# working.net
KiCad netlist of a schematic drawn in EAGLE
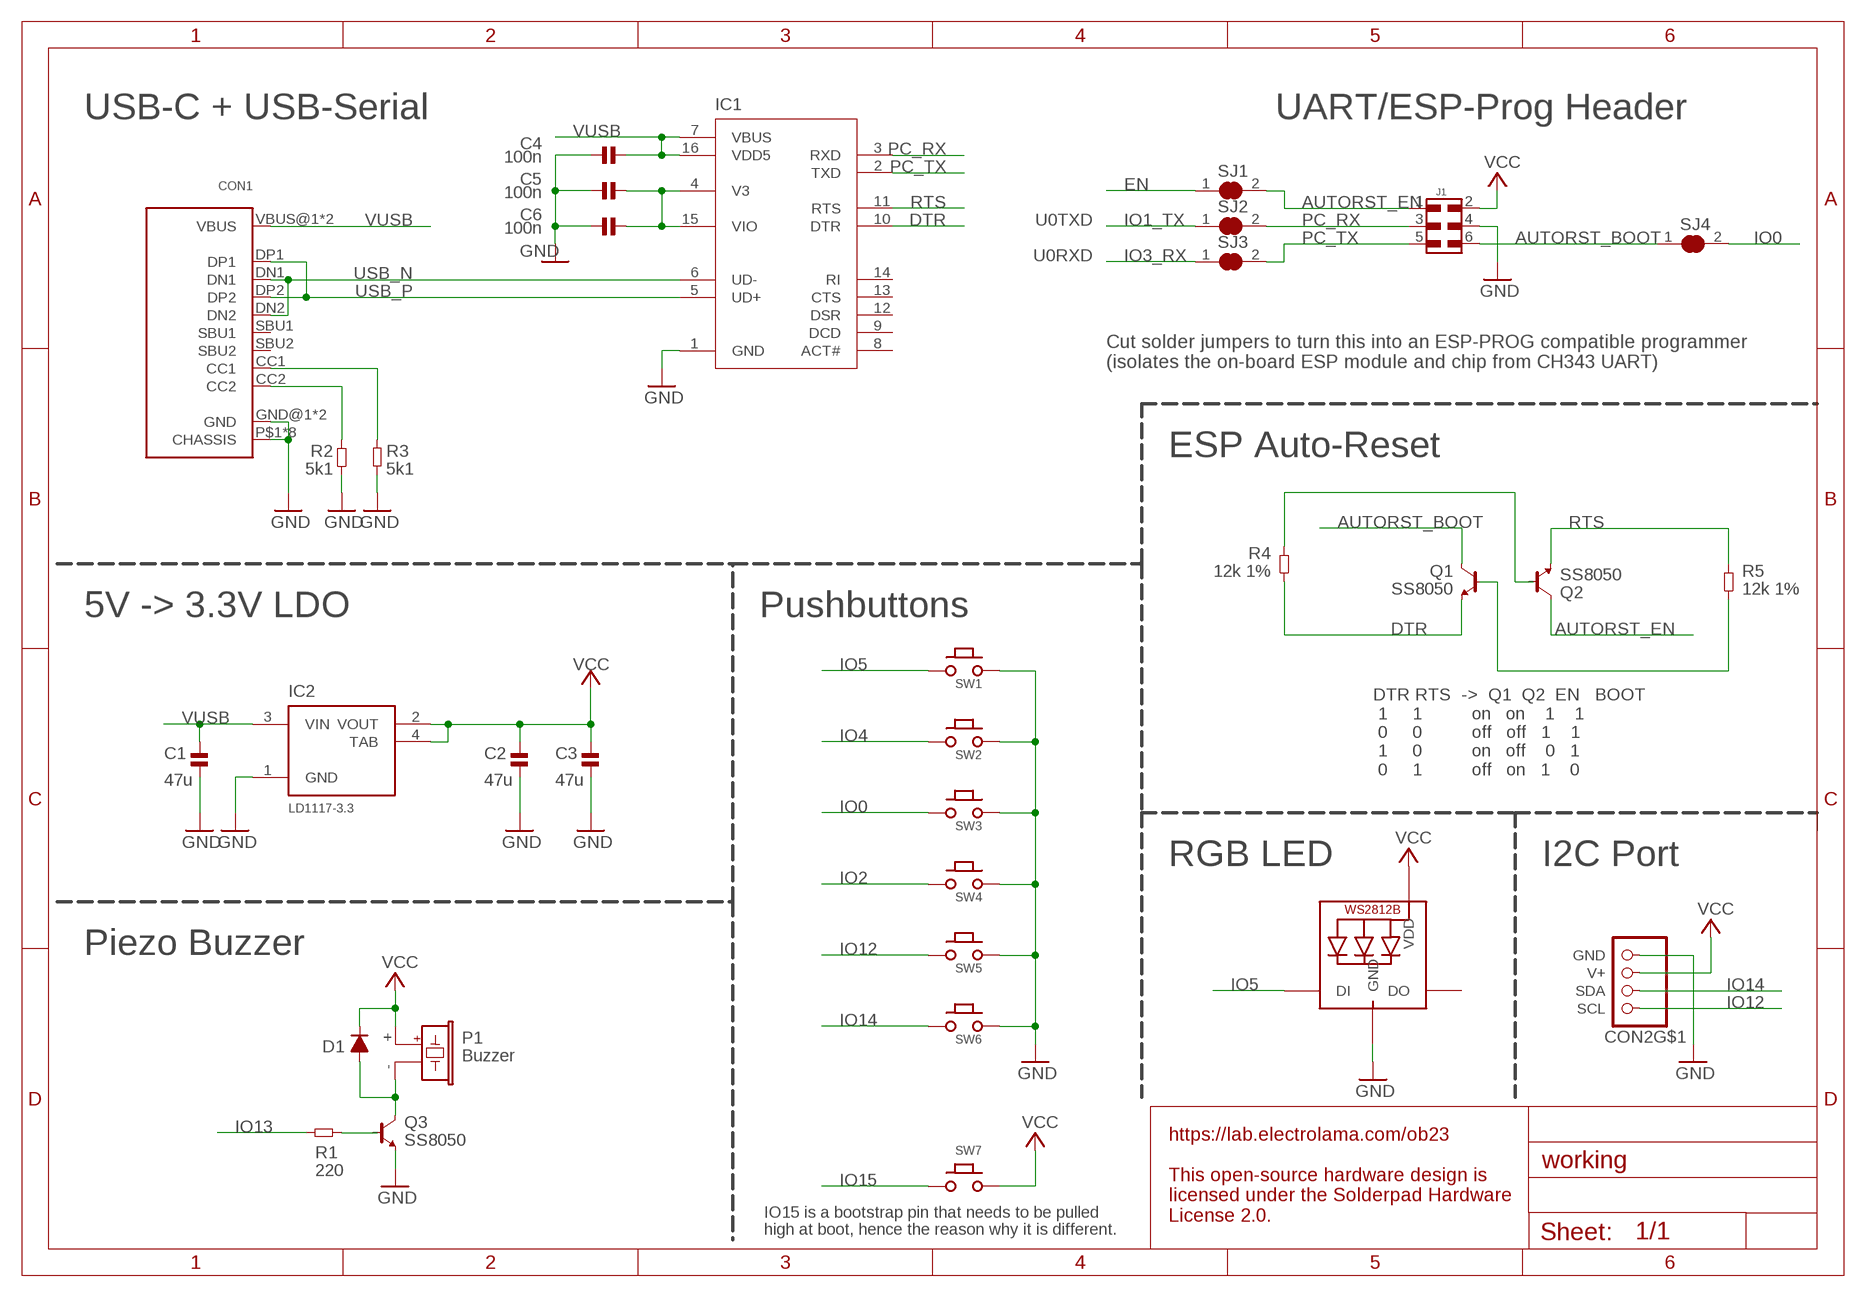
[diagram p0: schematic, sheet 1, part 1 of 2]
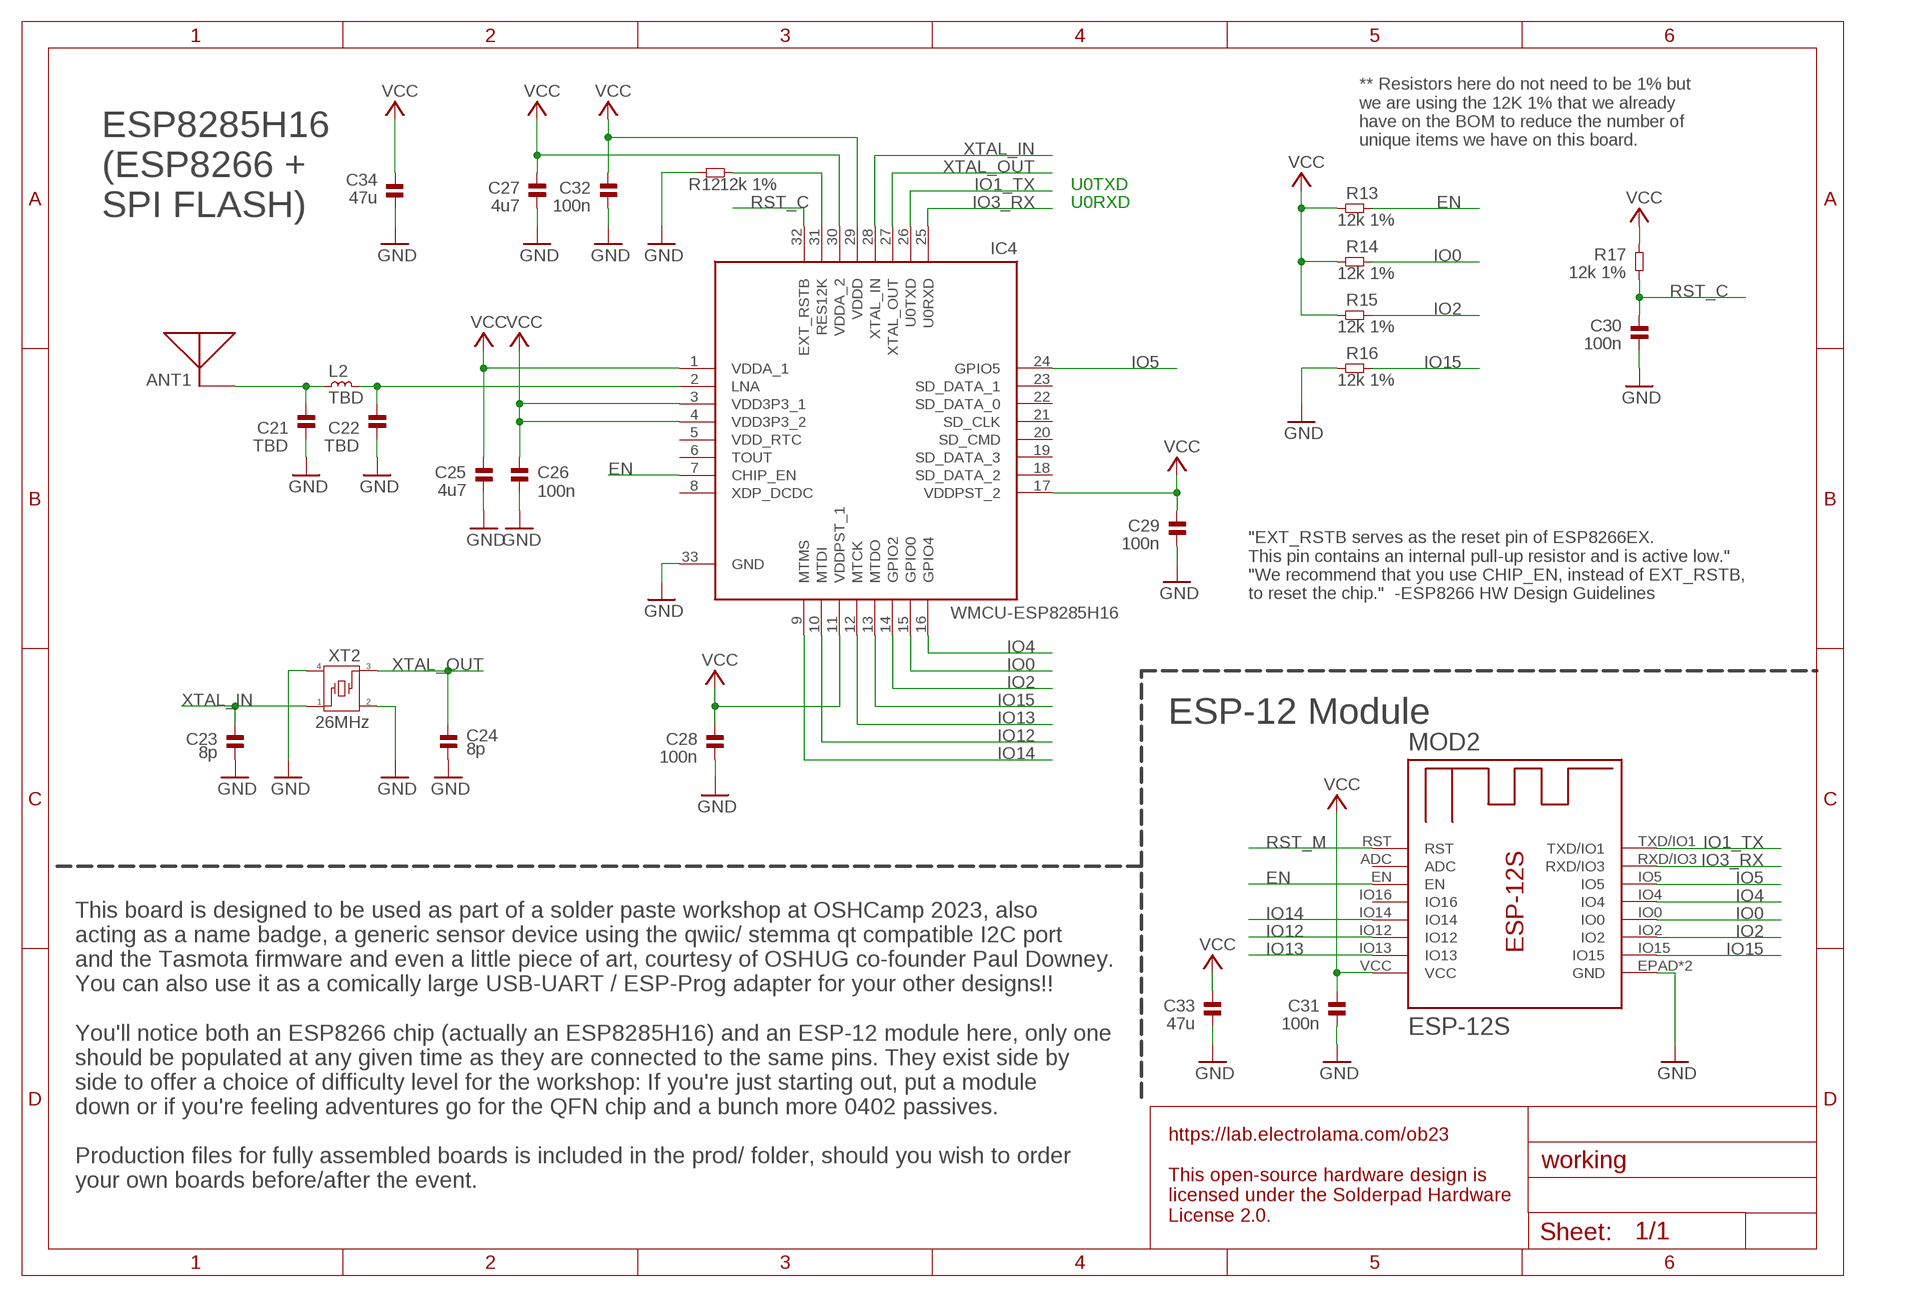
[diagram p1: schematic, sheet 1, part 2 of 2]

(export (version "E")
  (design (tool "Eeschema 10.0.6"))
  (components
    (comp (ref "ANT2")
      (value "ANT3216LL00R2400A")
      (footprint "eagle-import:YAGEO-ANT3216LL00R2400A")
      (libsource (lib "eagle-import") (part "ANT-CERAMIC-YAGEO-ANT3216LL00R2400A"))
    )
    (comp (ref "C1")
      (value "47u")
      (footprint "eagle-import:_PKG_C_1206")
      (fields (field (name "MPN") "CL31A476MPHNNNE"))
      (libsource (lib "eagle-import") (part "CAP-1206"))
    )
    (comp (ref "C2")
      (value "47u")
      (footprint "eagle-import:_PKG_C_1206")
      (fields (field (name "MPN") "CL31A476MPHNNNE"))
      (libsource (lib "eagle-import") (part "CAP-1206"))
    )
    (comp (ref "C3")
      (value "47u")
      (footprint "eagle-import:_PKG_C_1206")
      (fields (field (name "MPN") "CL31A476MPHNNNE"))
      (libsource (lib "eagle-import") (part "CAP-1206"))
    )
    (comp (ref "C4")
      (value "100n")
      (footprint "eagle-import:_PKG_C_0402")
      (libsource (lib "eagle-import") (part "CAP-0402"))
    )
    (comp (ref "C5")
      (value "100n")
      (footprint "eagle-import:_PKG_C_0402")
      (libsource (lib "eagle-import") (part "CAP-0402"))
    )
    (comp (ref "C6")
      (value "100n")
      (footprint "eagle-import:_PKG_C_0402")
      (libsource (lib "eagle-import") (part "CAP-0402"))
    )
    (comp (ref "C21")
      (value "TBD")
      (footprint "eagle-import:_PKG_C_0402_NOTHERMALS")
      (libsource (lib "eagle-import") (part "CAP-0402-NOTHERMALS"))
    )
    (comp (ref "C22")
      (value "TBD")
      (footprint "eagle-import:_PKG_C_0402_NOTHERMALS")
      (libsource (lib "eagle-import") (part "CAP-0402-NOTHERMALS"))
    )
    (comp (ref "C23")
      (value "8p")
      (footprint "eagle-import:_PKG_C_0402")
      (libsource (lib "eagle-import") (part "CAP-0402"))
    )
    (comp (ref "C24")
      (value "8p")
      (footprint "eagle-import:_PKG_C_0402")
      (libsource (lib "eagle-import") (part "CAP-0402"))
    )
    (comp (ref "C25")
      (value "4u7")
      (footprint "eagle-import:_PKG_C_0402_NOTHERMALS")
      (libsource (lib "eagle-import") (part "CAP-0402-NOTHERMALS"))
    )
    (comp (ref "C26")
      (value "100n")
      (footprint "eagle-import:_PKG_C_0402_NOTHERMALS")
      (libsource (lib "eagle-import") (part "CAP-0402-NOTHERMALS"))
    )
    (comp (ref "C27")
      (value "4u7")
      (footprint "eagle-import:_PKG_C_0402_NOTHERMALS")
      (libsource (lib "eagle-import") (part "CAP-0402-NOTHERMALS"))
    )
    (comp (ref "C28")
      (value "100n")
      (footprint "eagle-import:_PKG_C_0402_NOTHERMALS")
      (libsource (lib "eagle-import") (part "CAP-0402-NOTHERMALS"))
    )
    (comp (ref "C29")
      (value "100n")
      (footprint "eagle-import:_PKG_C_0402_NOTHERMALS")
      (libsource (lib "eagle-import") (part "CAP-0402-NOTHERMALS"))
    )
    (comp (ref "C30")
      (value "100n")
      (footprint "eagle-import:_PKG_C_0402_NOTHERMALS")
      (libsource (lib "eagle-import") (part "CAP-0402-NOTHERMALS"))
    )
    (comp (ref "C31")
      (value "100n")
      (footprint "eagle-import:_PKG_C_0402")
      (libsource (lib "eagle-import") (part "CAP-0402"))
    )
    (comp (ref "C32")
      (value "100n")
      (footprint "eagle-import:_PKG_C_0402_NOTHERMALS")
      (libsource (lib "eagle-import") (part "CAP-0402-NOTHERMALS"))
    )
    (comp (ref "C33")
      (value "47u")
      (footprint "eagle-import:_PKG_C_1206")
      (fields (field (name "MPN") "CL31A476MPHNNNE"))
      (libsource (lib "eagle-import") (part "CAP-1206"))
    )
    (comp (ref "C34")
      (value "47u")
      (footprint "eagle-import:_PKG_C_1206")
      (fields (field (name "MPN") "CL31A476MPHNNNE"))
      (libsource (lib "eagle-import") (part "CAP-1206"))
    )
    (comp (ref "CON1")
      (value "USBC_USB-C-12")
      (footprint "eagle-import:USBC_C-31-M-12")
      (libsource (lib "eagle-import") (part "USBC_USB-C-12"))
    )
    (comp (ref "CON2")
      (value "STEMMA_I2C_QT")
      (footprint "eagle-import:JST_SH4")
      (libsource (lib "eagle-import") (part "STEMMA_I2C_QT"))
    )
    (comp (ref "D1")
      (value "DIODE-SWITCHING-1N4148W")
      (footprint "eagle-import:_PKG_SOD123")
      (libsource (lib "eagle-import") (part "DIODE-SWITCHING-1N4148W"))
    )
    (comp (ref "IC1")
      (value "INTERFACE-CH343G")
      (footprint "eagle-import:_PKG_SOP16")
      (libsource (lib "eagle-import") (part "INTERFACE-CH343G"))
    )
    (comp (ref "IC2")
      (value "LD1117-3.3")
      (footprint "eagle-import:_PKG_SOT223-4_TI-DCY4")
      (libsource (lib "eagle-import") (part "POWER-LDO-LD1117-SOT223-4"))
    )
    (comp (ref "IC4")
      (value "WMCU-ESP8285H16")
      (footprint "eagle-import:QFN50P500X500X90-33N")
      (fields
        (field (name "MANUFACTURER_PART_NUMBER") "ESP8285H16")
        (field (name "MOUSER_PART_NUMBER") "356-ESP8285H16")
      )
      (libsource (lib "eagle-import") (part "WMCU-ESP8285H16"))
    )
    (comp (ref "J1")
      (value "61030621121")
      (footprint "eagle-import:61030621121")
      (libsource (lib "eagle-import") (part "6103XX21121_61030621121"))
    )
    (comp (ref "L2")
      (value "TBD")
      (footprint "eagle-import:_PKG_L_0402")
      (libsource (lib "eagle-import") (part "INDUCTOR-0402"))
    )
    (comp (ref "LED1")
      (value "WS2812B5050")
      (footprint "eagle-import:WS2812B")
      (libsource (lib "eagle-import") (part "WS2812B5050"))
    )
    (comp (ref "MOD2")
      (value "ESP-12S")
      (footprint "eagle-import:ESP-12S")
      (libsource (lib "eagle-import") (part "MODULE_ESP-12S"))
    )
    (comp (ref "P1")
      (value "Buzzer")
      (footprint "eagle-import:MLT-8530")
      (libsource (lib "eagle-import") (part "PIEZO-MLT-8530"))
    )
    (comp (ref "Q1")
      (value "SS8050")
      (footprint "eagle-import:SOT96P237X111-3N")
      (fields
        (field (name "ARROW_PART_NUMBER") "MMBT5550LT1G")
        (field (name "MOUSER_PART_NUMBER") "863-MMBT5550LT1G")
      )
      (libsource (lib "eagle-import") (part "NPN-MMBT5550LT1G"))
    )
    (comp (ref "Q2")
      (value "SS8050")
      (footprint "eagle-import:SOT96P237X111-3N")
      (fields
        (field (name "ARROW_PART_NUMBER") "MMBT5550LT1G")
        (field (name "MOUSER_PART_NUMBER") "863-MMBT5550LT1G")
      )
      (libsource (lib "eagle-import") (part "NPN-MMBT5550LT1G"))
    )
    (comp (ref "Q3")
      (value "SS8050")
      (footprint "eagle-import:SOT96P237X111-3N")
      (fields
        (field (name "ARROW_PART_NUMBER") "MMBT5550LT1G")
        (field (name "MOUSER_PART_NUMBER") "863-MMBT5550LT1G")
      )
      (libsource (lib "eagle-import") (part "NPN-MMBT5550LT1G"))
    )
    (comp (ref "R1")
      (value "220")
      (footprint "eagle-import:_PKG_R_0603")
      (libsource (lib "eagle-import") (part "RES-0603"))
    )
    (comp (ref "R2")
      (value "5k1")
      (footprint "eagle-import:_PKG_R_0603")
      (libsource (lib "eagle-import") (part "RES-0603"))
    )
    (comp (ref "R3")
      (value "5k1")
      (footprint "eagle-import:_PKG_R_0603")
      (libsource (lib "eagle-import") (part "RES-0603"))
    )
    (comp (ref "R4")
      (value "12k 1%")
      (footprint "eagle-import:_PKG_R_0402")
      (libsource (lib "eagle-import") (part "RES-0402"))
    )
    (comp (ref "R5")
      (value "12k 1%")
      (footprint "eagle-import:_PKG_R_0402")
      (libsource (lib "eagle-import") (part "RES-0402"))
    )
    (comp (ref "R12")
      (value "12k 1%")
      (footprint "eagle-import:_PKG_R_0402")
      (libsource (lib "eagle-import") (part "RES-0402"))
    )
    (comp (ref "R13")
      (value "12k 1%")
      (footprint "eagle-import:_PKG_R_0402")
      (libsource (lib "eagle-import") (part "RES-0402"))
    )
    (comp (ref "R14")
      (value "12k 1%")
      (footprint "eagle-import:_PKG_R_0402")
      (libsource (lib "eagle-import") (part "RES-0402"))
    )
    (comp (ref "R15")
      (value "12k 1%")
      (footprint "eagle-import:_PKG_R_0402")
      (libsource (lib "eagle-import") (part "RES-0402"))
    )
    (comp (ref "R16")
      (value "12k 1%")
      (footprint "eagle-import:_PKG_R_0402")
      (libsource (lib "eagle-import") (part "RES-0402"))
    )
    (comp (ref "R17")
      (value "12k 1%")
      (footprint "eagle-import:_PKG_R_0402")
      (libsource (lib "eagle-import") (part "RES-0402"))
    )
    (comp (ref "SJ1")
      (value "SJ-SHORT")
      (footprint "eagle-import:SJ-SHORT")
      (libsource (lib "eagle-import") (part "SJ-SHORT"))
    )
    (comp (ref "SJ2")
      (value "SJ-SHORT")
      (footprint "eagle-import:SJ-SHORT")
      (libsource (lib "eagle-import") (part "SJ-SHORT"))
    )
    (comp (ref "SJ3")
      (value "SJ-SHORT")
      (footprint "eagle-import:SJ-SHORT")
      (libsource (lib "eagle-import") (part "SJ-SHORT"))
    )
    (comp (ref "SJ4")
      (value "SJ-SHORT")
      (footprint "eagle-import:SJ-SHORT")
      (libsource (lib "eagle-import") (part "SJ-SHORT"))
    )
    (comp (ref "SW1")
      (value "PUSHBUTTON-6X6MM")
      (footprint "eagle-import:GENERIC_SPNO_4P_6X6MM")
      (libsource (lib "eagle-import") (part "PUSHBUTTON-6X6MM"))
    )
    (comp (ref "SW2")
      (value "PUSHBUTTON-6X6MM")
      (footprint "eagle-import:GENERIC_SPNO_4P_6X6MM")
      (libsource (lib "eagle-import") (part "PUSHBUTTON-6X6MM"))
    )
    (comp (ref "SW3")
      (value "PUSHBUTTON-6X6MM")
      (footprint "eagle-import:GENERIC_SPNO_4P_6X6MM")
      (libsource (lib "eagle-import") (part "PUSHBUTTON-6X6MM"))
    )
    (comp (ref "SW4")
      (value "PUSHBUTTON-6X6MM")
      (footprint "eagle-import:GENERIC_SPNO_4P_6X6MM")
      (libsource (lib "eagle-import") (part "PUSHBUTTON-6X6MM"))
    )
    (comp (ref "SW5")
      (value "PUSHBUTTON-6X6MM")
      (footprint "eagle-import:GENERIC_SPNO_4P_6X6MM")
      (libsource (lib "eagle-import") (part "PUSHBUTTON-6X6MM"))
    )
    (comp (ref "SW6")
      (value "PUSHBUTTON-6X6MM")
      (footprint "eagle-import:GENERIC_SPNO_4P_6X6MM")
      (libsource (lib "eagle-import") (part "PUSHBUTTON-6X6MM"))
    )
    (comp (ref "SW7")
      (value "PUSHBUTTON-6X6MM")
      (footprint "eagle-import:GENERIC_SPNO_4P_6X6MM")
      (libsource (lib "eagle-import") (part "PUSHBUTTON-6X6MM"))
    )
    (comp (ref "XT2")
      (value "26MHz")
      (footprint "eagle-import:XTAL-4P-2016")
      (libsource (lib "eagle-import") (part "XTAL-4P-2016"))
    )
  )
  (nets
    (net (code "1") (name "/AUTORST_BOOT") (class "Default")
      (node (ref "J1") (pin "6") (pinfunction "6_6") (pintype "passive"))
      (node (ref "Q1") (pin "3") (pinfunction "C_3") (pintype "passive"))
      (node (ref "SJ4") (pin "1") (pinfunction "1_1") (pintype "passive"))
    )
    (net (code "2") (name "/AUTORST_EN") (class "Default")
      (node (ref "J1") (pin "1") (pinfunction "1_1") (pintype "passive"))
      (node (ref "Q2") (pin "3") (pinfunction "C_3") (pintype "passive"))
      (node (ref "SJ1") (pin "2") (pinfunction "2_2") (pintype "passive"))
    )
    (net (code "3") (name "/DTR") (class "Default")
      (node (ref "IC1") (pin "10") (pinfunction "DTR_10") (pintype "bidirectional"))
      (node (ref "Q1") (pin "2") (pinfunction "E_2") (pintype "passive"))
      (node (ref "R4") (pin "1") (pinfunction "1_1") (pintype "passive"))
    )
    (net (code "4") (name "/EN") (class "Default")
      (node (ref "IC4") (pin "7") (pinfunction "CHIP_EN_7") (pintype "bidirectional"))
      (node (ref "MOD2") (pin "EN") (pinfunction "EN_EN") (pintype "bidirectional"))
      (node (ref "R13") (pin "2") (pinfunction "2_2") (pintype "passive"))
      (node (ref "SJ1") (pin "1") (pinfunction "1_1") (pintype "passive"))
    )
    (net (code "5") (name "/IO0") (class "Default")
      (node (ref "IC4") (pin "15") (pinfunction "GPIO0_15") (pintype "bidirectional"))
      (node (ref "MOD2") (pin "IO0") (pinfunction "IO0_IO0") (pintype "bidirectional"))
      (node (ref "R14") (pin "2") (pinfunction "2_2") (pintype "passive"))
      (node (ref "SJ4") (pin "2") (pinfunction "2_2") (pintype "passive"))
      (node (ref "SW3") (pin "P$1") (pinfunction "1_P$1") (pintype "bidirectional"))
      (node (ref "SW3") (pin "P$2") (pinfunction "1_P$2") (pintype "bidirectional"))
    )
    (net (code "6") (name "/IO1_TX") (class "Default")
      (node (ref "IC4") (pin "26") (pinfunction "U0TXD_26") (pintype "bidirectional"))
      (node (ref "MOD2") (pin "TXD/IO1") (pinfunction "TXD/IO1_TXD/IO1") (pintype "bidirectional"))
      (node (ref "SJ2") (pin "1") (pinfunction "1_1") (pintype "passive"))
    )
    (net (code "7") (name "/IO2") (class "Default")
      (node (ref "IC4") (pin "14") (pinfunction "GPIO2_14") (pintype "bidirectional"))
      (node (ref "MOD2") (pin "IO2") (pinfunction "IO2_IO2") (pintype "bidirectional"))
      (node (ref "R15") (pin "2") (pinfunction "2_2") (pintype "passive"))
      (node (ref "SW4") (pin "P$1") (pinfunction "1_P$1") (pintype "bidirectional"))
      (node (ref "SW4") (pin "P$2") (pinfunction "1_P$2") (pintype "bidirectional"))
    )
    (net (code "8") (name "/IO3_RX") (class "Default")
      (node (ref "IC4") (pin "25") (pinfunction "U0RXD_25") (pintype "bidirectional"))
      (node (ref "MOD2") (pin "RXD/IO3") (pinfunction "RXD/IO3_RXD/IO3") (pintype "bidirectional"))
      (node (ref "SJ3") (pin "1") (pinfunction "1_1") (pintype "passive"))
    )
    (net (code "9") (name "/IO4") (class "Default")
      (node (ref "IC4") (pin "16") (pinfunction "GPIO4_16") (pintype "bidirectional"))
      (node (ref "MOD2") (pin "IO4") (pinfunction "IO4_IO4") (pintype "bidirectional"))
      (node (ref "SW2") (pin "P$1") (pinfunction "1_P$1") (pintype "bidirectional"))
      (node (ref "SW2") (pin "P$2") (pinfunction "1_P$2") (pintype "bidirectional"))
    )
    (net (code "10") (name "/IO5") (class "Default")
      (node (ref "IC4") (pin "24") (pinfunction "GPIO5_24") (pintype "bidirectional"))
      (node (ref "LED1") (pin "4-DIN") (pinfunction "DI_4-DIN") (pintype "input"))
      (node (ref "MOD2") (pin "IO5") (pinfunction "IO5_IO5") (pintype "bidirectional"))
      (node (ref "SW1") (pin "P$1") (pinfunction "1_P$1") (pintype "bidirectional"))
      (node (ref "SW1") (pin "P$2") (pinfunction "1_P$2") (pintype "bidirectional"))
    )
    (net (code "11") (name "/IO12") (class "Default")
      (node (ref "CON2") (pin "4") (pinfunction "SCL_4") (pintype "passive"))
      (node (ref "IC4") (pin "10") (pinfunction "MTDI_10") (pintype "bidirectional"))
      (node (ref "MOD2") (pin "IO12") (pinfunction "IO12_IO12") (pintype "bidirectional"))
      (node (ref "SW5") (pin "P$1") (pinfunction "1_P$1") (pintype "bidirectional"))
      (node (ref "SW5") (pin "P$2") (pinfunction "1_P$2") (pintype "bidirectional"))
    )
    (net (code "12") (name "/IO13") (class "Default")
      (node (ref "IC4") (pin "12") (pinfunction "MTCK_12") (pintype "bidirectional"))
      (node (ref "MOD2") (pin "IO13") (pinfunction "IO13_IO13") (pintype "bidirectional"))
      (node (ref "R1") (pin "2") (pinfunction "2_2") (pintype "passive"))
    )
    (net (code "13") (name "/IO14") (class "Default")
      (node (ref "CON2") (pin "3") (pinfunction "SDA_3") (pintype "passive"))
      (node (ref "IC4") (pin "9") (pinfunction "MTMS_9") (pintype "bidirectional"))
      (node (ref "MOD2") (pin "IO14") (pinfunction "IO14_IO14") (pintype "bidirectional"))
      (node (ref "SW6") (pin "P$1") (pinfunction "1_P$1") (pintype "bidirectional"))
      (node (ref "SW6") (pin "P$2") (pinfunction "1_P$2") (pintype "bidirectional"))
    )
    (net (code "14") (name "/IO15") (class "Default")
      (node (ref "IC4") (pin "13") (pinfunction "MTDO_13") (pintype "bidirectional"))
      (node (ref "MOD2") (pin "IO15") (pinfunction "IO15_IO15") (pintype "bidirectional"))
      (node (ref "R16") (pin "2") (pinfunction "2_2") (pintype "passive"))
      (node (ref "SW7") (pin "P$1") (pinfunction "1_P$1") (pintype "bidirectional"))
      (node (ref "SW7") (pin "P$2") (pinfunction "1_P$2") (pintype "bidirectional"))
    )
    (net (code "15") (name "/PC_RX") (class "Default")
      (node (ref "IC1") (pin "3") (pinfunction "RXD_3") (pintype "bidirectional"))
      (node (ref "J1") (pin "3") (pinfunction "3_3") (pintype "passive"))
      (node (ref "SJ2") (pin "2") (pinfunction "2_2") (pintype "passive"))
    )
    (net (code "16") (name "/PC_TX") (class "Default")
      (node (ref "IC1") (pin "2") (pinfunction "TXD_2") (pintype "bidirectional"))
      (node (ref "J1") (pin "5") (pinfunction "5_5") (pintype "passive"))
      (node (ref "SJ3") (pin "2") (pinfunction "2_2") (pintype "passive"))
    )
    (net (code "17") (name "/RST_C") (class "Default")
      (node (ref "C30") (pin "2") (pinfunction "2_2") (pintype "passive"))
      (node (ref "IC4") (pin "32") (pinfunction "EXT_RSTB_32") (pintype "bidirectional"))
      (node (ref "R17") (pin "1") (pinfunction "1_1") (pintype "passive"))
    )
    (net (code "18") (name "/RST_M") (class "Default")
      (node (ref "MOD2") (pin "RST") (pinfunction "RST_RST") (pintype "input"))
    )
    (net (code "19") (name "/RTS") (class "Default")
      (node (ref "IC1") (pin "11") (pinfunction "RTS_11") (pintype "bidirectional"))
      (node (ref "Q2") (pin "2") (pinfunction "E_2") (pintype "passive"))
      (node (ref "R5") (pin "2") (pinfunction "2_2") (pintype "passive"))
    )
    (net (code "20") (name "/USB_N") (class "Default")
      (node (ref "CON1") (pin "DN1") (pinfunction "DN1_DN1") (pintype "bidirectional"))
      (node (ref "CON1") (pin "DN2") (pinfunction "DN2_DN2") (pintype "bidirectional"))
      (node (ref "IC1") (pin "6") (pinfunction "UD-_6") (pintype "bidirectional"))
    )
    (net (code "21") (name "/USB_P") (class "Default")
      (node (ref "CON1") (pin "DP1") (pinfunction "DP1_DP1") (pintype "bidirectional"))
      (node (ref "CON1") (pin "DP2") (pinfunction "DP2_DP2") (pintype "bidirectional"))
      (node (ref "IC1") (pin "5") (pinfunction "UD+_5") (pintype "bidirectional"))
    )
    (net (code "22") (name "/VUSB") (class "Default")
      (node (ref "C1") (pin "1") (pinfunction "1_1") (pintype "passive"))
      (node (ref "C4") (pin "1") (pinfunction "1_1") (pintype "passive"))
      (node (ref "CON1") (pin "VBUS@1") (pinfunction "VBUS_VBUS@1") (pintype "bidirectional"))
      (node (ref "CON1") (pin "VBUS@2") (pinfunction "VBUS_VBUS@2") (pintype "bidirectional"))
      (node (ref "IC1") (pin "16") (pinfunction "VDD5_16") (pintype "bidirectional"))
      (node (ref "IC1") (pin "7") (pinfunction "VBUS_7") (pintype "bidirectional"))
      (node (ref "IC2") (pin "3") (pinfunction "VIN_3") (pintype "output"))
    )
    (net (code "23") (name "/XTAL_IN") (class "Default")
      (node (ref "C23") (pin "2") (pinfunction "2_2") (pintype "passive"))
      (node (ref "IC4") (pin "28") (pinfunction "XTAL_IN_28") (pintype "bidirectional"))
      (node (ref "XT2") (pin "1") (pinfunction "1_1") (pintype "passive"))
    )
    (net (code "24") (name "/XTAL_OUT") (class "Default")
      (node (ref "C24") (pin "2") (pinfunction "2_2") (pintype "passive"))
      (node (ref "IC4") (pin "27") (pinfunction "XTAL_OUT_27") (pintype "bidirectional"))
      (node (ref "XT2") (pin "3") (pinfunction "3_3") (pintype "passive"))
    )
    (net (code "25") (name "GND") (class "Default")
      (node (ref "C1") (pin "2") (pinfunction "2_2") (pintype "passive"))
      (node (ref "C2") (pin "2") (pinfunction "2_2") (pintype "passive"))
      (node (ref "C21") (pin "1") (pinfunction "1_1") (pintype "passive"))
      (node (ref "C22") (pin "1") (pinfunction "1_1") (pintype "passive"))
      (node (ref "C23") (pin "1") (pinfunction "1_1") (pintype "passive"))
      (node (ref "C24") (pin "1") (pinfunction "1_1") (pintype "passive"))
      (node (ref "C25") (pin "1") (pinfunction "1_1") (pintype "passive"))
      (node (ref "C26") (pin "1") (pinfunction "1_1") (pintype "passive"))
      (node (ref "C27") (pin "1") (pinfunction "1_1") (pintype "passive"))
      (node (ref "C28") (pin "1") (pinfunction "1_1") (pintype "passive"))
      (node (ref "C29") (pin "1") (pinfunction "1_1") (pintype "passive"))
      (node (ref "C3") (pin "2") (pinfunction "2_2") (pintype "passive"))
      (node (ref "C30") (pin "1") (pinfunction "1_1") (pintype "passive"))
      (node (ref "C31") (pin "2") (pinfunction "2_2") (pintype "passive"))
      (node (ref "C32") (pin "1") (pinfunction "1_1") (pintype "passive"))
      (node (ref "C33") (pin "2") (pinfunction "2_2") (pintype "passive"))
      (node (ref "C34") (pin "2") (pinfunction "2_2") (pintype "passive"))
      (node (ref "C4") (pin "2") (pinfunction "2_2") (pintype "passive"))
      (node (ref "C5") (pin "2") (pinfunction "2_2") (pintype "passive"))
      (node (ref "C6") (pin "2") (pinfunction "2_2") (pintype "passive"))
      (node (ref "CON1") (pin "GND@1") (pinfunction "GND_GND@1") (pintype "bidirectional"))
      (node (ref "CON1") (pin "GND@2") (pinfunction "GND_GND@2") (pintype "bidirectional"))
      (node (ref "CON1") (pin "P$1") (pinfunction "CHASSIS_P$1") (pintype "bidirectional"))
      (node (ref "CON1") (pin "P$2") (pinfunction "CHASSIS_P$2") (pintype "bidirectional"))
      (node (ref "CON1") (pin "P$3") (pinfunction "CHASSIS_P$3") (pintype "bidirectional"))
      (node (ref "CON1") (pin "P$4") (pinfunction "CHASSIS_P$4") (pintype "bidirectional"))
      (node (ref "CON1") (pin "P$5") (pinfunction "CHASSIS_P$5") (pintype "bidirectional"))
      (node (ref "CON1") (pin "P$6") (pinfunction "CHASSIS_P$6") (pintype "bidirectional"))
      (node (ref "CON1") (pin "P$7") (pinfunction "CHASSIS_P$7") (pintype "bidirectional"))
      (node (ref "CON1") (pin "P$8") (pinfunction "CHASSIS_P$8") (pintype "bidirectional"))
      (node (ref "CON2") (pin "1") (pinfunction "GND_1") (pintype "passive"))
      (node (ref "IC1") (pin "1") (pinfunction "GND_1") (pintype "bidirectional"))
      (node (ref "IC2") (pin "1") (pinfunction "GND_1") (pintype "output"))
      (node (ref "IC4") (pin "33") (pinfunction "GND_33") (pintype "bidirectional"))
      (node (ref "J1") (pin "4") (pinfunction "4_4") (pintype "passive"))
      (node (ref "LED1") (pin "3-GND") (pinfunction "GND_3-GND") (pintype "power_in"))
      (node (ref "MOD2") (pin "EPAD") (pinfunction "GND_EPAD") (pintype "power_in"))
      (node (ref "MOD2") (pin "GND") (pinfunction "GND_GND") (pintype "power_in"))
      (node (ref "Q3") (pin "2") (pinfunction "E_2") (pintype "passive"))
      (node (ref "R12") (pin "2") (pinfunction "2_2") (pintype "passive"))
      (node (ref "R16") (pin "1") (pinfunction "1_1") (pintype "passive"))
      (node (ref "R2") (pin "1") (pinfunction "1_1") (pintype "passive"))
      (node (ref "R3") (pin "1") (pinfunction "1_1") (pintype "passive"))
      (node (ref "SW1") (pin "P$3") (pinfunction "2_P$3") (pintype "bidirectional"))
      (node (ref "SW1") (pin "P$4") (pinfunction "2_P$4") (pintype "bidirectional"))
      (node (ref "SW2") (pin "P$3") (pinfunction "2_P$3") (pintype "bidirectional"))
      (node (ref "SW2") (pin "P$4") (pinfunction "2_P$4") (pintype "bidirectional"))
      (node (ref "SW3") (pin "P$3") (pinfunction "2_P$3") (pintype "bidirectional"))
      (node (ref "SW3") (pin "P$4") (pinfunction "2_P$4") (pintype "bidirectional"))
      (node (ref "SW4") (pin "P$3") (pinfunction "2_P$3") (pintype "bidirectional"))
      (node (ref "SW4") (pin "P$4") (pinfunction "2_P$4") (pintype "bidirectional"))
      (node (ref "SW5") (pin "P$3") (pinfunction "2_P$3") (pintype "bidirectional"))
      (node (ref "SW5") (pin "P$4") (pinfunction "2_P$4") (pintype "bidirectional"))
      (node (ref "SW6") (pin "P$3") (pinfunction "2_P$3") (pintype "bidirectional"))
      (node (ref "SW6") (pin "P$4") (pinfunction "2_P$4") (pintype "bidirectional"))
      (node (ref "XT2") (pin "2") (pinfunction "2_2") (pintype "bidirectional"))
      (node (ref "XT2") (pin "4") (pinfunction "4_4") (pintype "bidirectional"))
    )
    (net (code "26") (name "Net-(ANT2-FEED)") (class "Default")
      (node (ref "ANT2") (pin "S1") (pinfunction "FEED_S1") (pintype "bidirectional"))
      (node (ref "C21") (pin "2") (pinfunction "2_2") (pintype "passive"))
      (node (ref "L2") (pin "1") (pinfunction "1_1") (pintype "passive"))
    )
    (net (code "27") (name "Net-(CON1-PadCC1)") (class "Default")
      (node (ref "CON1") (pin "CC1") (pinfunction "CC1_CC1") (pintype "bidirectional"))
      (node (ref "R3") (pin "2") (pinfunction "2_2") (pintype "passive"))
    )
    (net (code "28") (name "Net-(CON1-PadCC2)") (class "Default")
      (node (ref "CON1") (pin "CC2") (pinfunction "CC2_CC2") (pintype "bidirectional"))
      (node (ref "R2") (pin "2") (pinfunction "2_2") (pintype "passive"))
    )
    (net (code "29") (name "Net-(D1-A)") (class "Default")
      (node (ref "D1") (pin "2") (pinfunction "A_2") (pintype "passive"))
      (node (ref "P1") (pin "-") (pinfunction "-_-") (pintype "passive"))
      (node (ref "Q3") (pin "3") (pinfunction "C_3") (pintype "passive"))
    )
    (net (code "30") (name "Net-(IC1-V3)") (class "Default")
      (node (ref "C5") (pin "1") (pinfunction "1_1") (pintype "passive"))
      (node (ref "C6") (pin "1") (pinfunction "1_1") (pintype "passive"))
      (node (ref "IC1") (pin "15") (pinfunction "VIO_15") (pintype "bidirectional"))
      (node (ref "IC1") (pin "4") (pinfunction "V3_4") (pintype "bidirectional"))
    )
    (net (code "31") (name "Net-(IC4-LNA)") (class "Default")
      (node (ref "C22") (pin "2") (pinfunction "2_2") (pintype "passive"))
      (node (ref "IC4") (pin "2") (pinfunction "LNA_2") (pintype "bidirectional"))
      (node (ref "L2") (pin "2") (pinfunction "2_2") (pintype "passive"))
    )
    (net (code "32") (name "Net-(IC4-RES12K)") (class "Default")
      (node (ref "IC4") (pin "31") (pinfunction "RES12K_31") (pintype "bidirectional"))
      (node (ref "R12") (pin "1") (pinfunction "1_1") (pintype "passive"))
    )
    (net (code "33") (name "Net-(Q1-B)") (class "Default")
      (node (ref "Q1") (pin "1") (pinfunction "B_1") (pintype "passive"))
      (node (ref "R5") (pin "1") (pinfunction "1_1") (pintype "passive"))
    )
    (net (code "34") (name "Net-(Q2-B)") (class "Default")
      (node (ref "Q2") (pin "1") (pinfunction "B_1") (pintype "passive"))
      (node (ref "R4") (pin "2") (pinfunction "2_2") (pintype "passive"))
    )
    (net (code "35") (name "Net-(Q3-B)") (class "Default")
      (node (ref "Q3") (pin "1") (pinfunction "B_1") (pintype "passive"))
      (node (ref "R1") (pin "1") (pinfunction "1_1") (pintype "passive"))
    )
    (net (code "36") (name "VCC") (class "Default")
      (node (ref "C2") (pin "1") (pinfunction "1_1") (pintype "passive"))
      (node (ref "C25") (pin "2") (pinfunction "2_2") (pintype "passive"))
      (node (ref "C26") (pin "2") (pinfunction "2_2") (pintype "passive"))
      (node (ref "C27") (pin "2") (pinfunction "2_2") (pintype "passive"))
      (node (ref "C28") (pin "2") (pinfunction "2_2") (pintype "passive"))
      (node (ref "C29") (pin "2") (pinfunction "2_2") (pintype "passive"))
      (node (ref "C3") (pin "1") (pinfunction "1_1") (pintype "passive"))
      (node (ref "C31") (pin "1") (pinfunction "1_1") (pintype "passive"))
      (node (ref "C32") (pin "2") (pinfunction "2_2") (pintype "passive"))
      (node (ref "C33") (pin "1") (pinfunction "1_1") (pintype "passive"))
      (node (ref "C34") (pin "1") (pinfunction "1_1") (pintype "passive"))
      (node (ref "CON2") (pin "2") (pinfunction "V+_2") (pintype "passive"))
      (node (ref "D1") (pin "1") (pinfunction "C_1") (pintype "passive"))
      (node (ref "IC2") (pin "2") (pinfunction "VOUT_2") (pintype "output"))
      (node (ref "IC2") (pin "4") (pinfunction "TAB_4") (pintype "output"))
      (node (ref "IC4") (pin "1") (pinfunction "VDDA_1_1") (pintype "bidirectional"))
      (node (ref "IC4") (pin "11") (pinfunction "VDDPST_1_11") (pintype "bidirectional"))
      (node (ref "IC4") (pin "17") (pinfunction "VDDPST_2_17") (pintype "bidirectional"))
      (node (ref "IC4") (pin "29") (pinfunction "VDDD_29") (pintype "bidirectional"))
      (node (ref "IC4") (pin "3") (pinfunction "VDD3P3_1_3") (pintype "bidirectional"))
      (node (ref "IC4") (pin "30") (pinfunction "VDDA_2_30") (pintype "bidirectional"))
      (node (ref "IC4") (pin "4") (pinfunction "VDD3P3_2_4") (pintype "bidirectional"))
      (node (ref "J1") (pin "2") (pinfunction "2_2") (pintype "passive"))
      (node (ref "LED1") (pin "1-VDD") (pinfunction "VDD_1-VDD") (pintype "power_in"))
      (node (ref "MOD2") (pin "VCC") (pinfunction "VCC_VCC") (pintype "power_in"))
      (node (ref "P1") (pin "+") (pinfunction "+_+") (pintype "passive"))
      (node (ref "R13") (pin "1") (pinfunction "1_1") (pintype "passive"))
      (node (ref "R14") (pin "1") (pinfunction "1_1") (pintype "passive"))
      (node (ref "R15") (pin "1") (pinfunction "1_1") (pintype "passive"))
      (node (ref "R17") (pin "2") (pinfunction "2_2") (pintype "passive"))
      (node (ref "SW7") (pin "P$3") (pinfunction "2_P$3") (pintype "bidirectional"))
      (node (ref "SW7") (pin "P$4") (pinfunction "2_P$4") (pintype "bidirectional"))
    )
    (net (code "37") (name "unconnected-(CON1-PadSBU1)") (class "Default")
      (node (ref "CON1") (pin "SBU1") (pinfunction "SBU1_SBU1") (pintype "bidirectional"))
    )
    (net (code "38") (name "unconnected-(CON1-PadSBU2)") (class "Default")
      (node (ref "CON1") (pin "SBU2") (pinfunction "SBU2_SBU2") (pintype "bidirectional"))
    )
    (net (code "39") (name "unconnected-(IC1-ACT#-Pad8)") (class "Default")
      (node (ref "IC1") (pin "8") (pinfunction "ACT#_8") (pintype "bidirectional"))
    )
    (net (code "40") (name "unconnected-(IC1-CTS-Pad13)") (class "Default")
      (node (ref "IC1") (pin "13") (pinfunction "CTS_13") (pintype "bidirectional"))
    )
    (net (code "41") (name "unconnected-(IC1-DCD-Pad9)") (class "Default")
      (node (ref "IC1") (pin "9") (pinfunction "DCD_9") (pintype "bidirectional"))
    )
    (net (code "42") (name "unconnected-(IC1-DSR-Pad12)") (class "Default")
      (node (ref "IC1") (pin "12") (pinfunction "DSR_12") (pintype "bidirectional"))
    )
    (net (code "43") (name "unconnected-(IC1-RI-Pad14)") (class "Default")
      (node (ref "IC1") (pin "14") (pinfunction "RI_14") (pintype "bidirectional"))
    )
    (net (code "44") (name "unconnected-(IC4-SD_CLK-Pad21)") (class "Default")
      (node (ref "IC4") (pin "21") (pinfunction "SD_CLK_21") (pintype "bidirectional"))
    )
    (net (code "45") (name "unconnected-(IC4-SD_CMD-Pad20)") (class "Default")
      (node (ref "IC4") (pin "20") (pinfunction "SD_CMD_20") (pintype "bidirectional"))
    )
    (net (code "46") (name "unconnected-(IC4-SD_DATA_0-Pad22)") (class "Default")
      (node (ref "IC4") (pin "22") (pinfunction "SD_DATA_0_22") (pintype "bidirectional"))
    )
    (net (code "47") (name "unconnected-(IC4-SD_DATA_1-Pad23)") (class "Default")
      (node (ref "IC4") (pin "23") (pinfunction "SD_DATA_1_23") (pintype "bidirectional"))
    )
    (net (code "48") (name "unconnected-(IC4-SD_DATA_2-Pad18)") (class "Default")
      (node (ref "IC4") (pin "18") (pinfunction "SD_DATA_2_18") (pintype "bidirectional"))
    )
    (net (code "49") (name "unconnected-(IC4-SD_DATA_3-Pad19)") (class "Default")
      (node (ref "IC4") (pin "19") (pinfunction "SD_DATA_3_19") (pintype "bidirectional"))
    )
    (net (code "50") (name "unconnected-(IC4-TOUT-Pad6)") (class "Default")
      (node (ref "IC4") (pin "6") (pinfunction "TOUT_6") (pintype "bidirectional"))
    )
    (net (code "51") (name "unconnected-(IC4-VDD_RTC-Pad5)") (class "Default")
      (node (ref "IC4") (pin "5") (pinfunction "VDD_RTC_5") (pintype "bidirectional"))
    )
    (net (code "52") (name "unconnected-(IC4-XDP_DCDC-Pad8)") (class "Default")
      (node (ref "IC4") (pin "8") (pinfunction "XDP_DCDC_8") (pintype "bidirectional"))
    )
    (net (code "53") (name "unconnected-(LED1-DO-Pad2-DOUT)") (class "Default")
      (node (ref "LED1") (pin "2-DOUT") (pinfunction "DO_2-DOUT") (pintype "output"))
    )
    (net (code "54") (name "unconnected-(MOD2-PadADC)") (class "Default")
      (node (ref "MOD2") (pin "ADC") (pinfunction "ADC_ADC") (pintype "bidirectional"))
    )
    (net (code "55") (name "unconnected-(MOD2-PadIO16)") (class "Default")
      (node (ref "MOD2") (pin "IO16") (pinfunction "IO16_IO16") (pintype "bidirectional"))
    )
  )
)
